# LED.net
KiCad netlist of a schematic drawn in Altium Designer
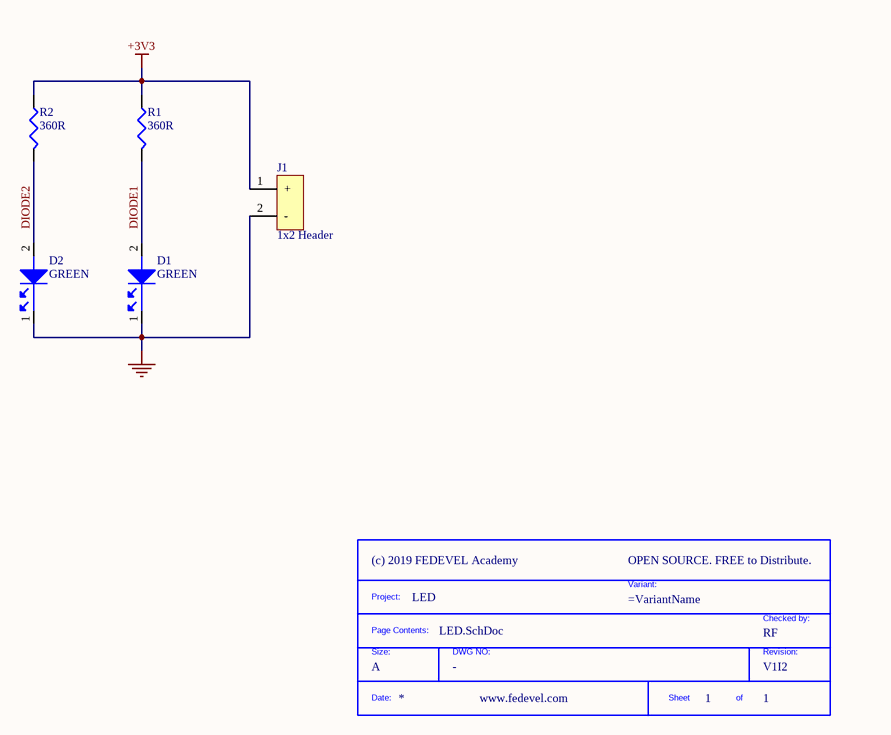
[diagram p0: LED.SchDoc]

(export (version "E")
  (design (tool "Eeschema 10.0.6"))
  (components
    (comp (ref "*")
      (value "TitleBlock")
      (description "Standard Title Block")
      (fields (field (name "DWG NO") "-") (field (name "SIZE") "A") (field (name "CHECKED BY") "RF"))
      (libsource (lib "LED_SchLib") (part "TitleBlock"))
    )
    (comp (ref "D1")
      (value "GREEN")
      (footprint "LED0603G")
      (description "Standard LEDs - SMD LED GR HI-BRT USS")
      (fields
        (field (name "MANUFACTURER") "Panasonic SSG")
        (field (name "MANUFACTURER PART NUMBER") "LNJ337W83RA")
      )
      (libsource (lib "LED_SchLib") (part "LNJ337W83RA"))
    )
    (comp (ref "D2")
      (value "GREEN")
      (footprint "LED0603G")
      (description "Standard LEDs - SMD LED GR HI-BRT USS")
      (fields
        (field (name "MANUFACTURER") "Panasonic SSG")
        (field (name "MANUFACTURER PART NUMBER") "LNJ337W83RA")
      )
      (libsource (lib "LED_SchLib") (part "LNJ337W83RA"))
    )
    (comp (ref "J1")
      (value "1x2 Header")
      (footprint "HDR1X2")
      (description "Headers & Wire Housings 2 PIN F/LK HEADER")
      (fields (field (name "MANUFACTURER") "Molex") (field (name "MANUFACTURER PART NUMBER") "22-29-2021"))
      (libsource (lib "LED_SchLib") (part "22-29-2021"))
    )
    (comp (ref "R1")
      (value "360R")
      (footprint "R0805")
      (description "RES SMD 360 OHM 1% 1/8W 0805")
      (fields
        (field (name "MANUFACTURER") "Vishay")
        (field (name "MANUFACTURER PART NUMBER") "CRCW0805360RFKEA")
      )
      (libsource (lib "LED_SchLib") (part "CRCW0805360RFKEA"))
    )
    (comp (ref "R2")
      (value "360R")
      (footprint "R0805")
      (description "RES SMD 360 OHM 1% 1/8W 0805")
      (fields
        (field (name "MANUFACTURER") "Vishay")
        (field (name "MANUFACTURER PART NUMBER") "CRCW0805360RFKEA")
      )
      (libsource (lib "LED_SchLib") (part "CRCW0805360RFKEA"))
    )
  )
  (nets
    (net (code "1") (name "+3V3") (class "Default")
      (node (ref "J1") (pin "1") (pinfunction "+_1") (pintype "passive"))
      (node (ref "R1") (pin "1") (pinfunction "1_1") (pintype "passive"))
      (node (ref "R2") (pin "1") (pinfunction "1_1") (pintype "passive"))
    )
    (net (code "2") (name "/DIODE1") (class "Default")
      (node (ref "D1") (pin "2") (pinfunction "2_2") (pintype "passive"))
      (node (ref "R1") (pin "2") (pinfunction "2_2") (pintype "passive"))
    )
    (net (code "3") (name "/DIODE2") (class "Default")
      (node (ref "D2") (pin "2") (pinfunction "2_2") (pintype "passive"))
      (node (ref "R2") (pin "2") (pinfunction "2_2") (pintype "passive"))
    )
    (net (code "4") (name "GND") (class "Default")
      (node (ref "D1") (pin "1") (pinfunction "1_1") (pintype "passive"))
      (node (ref "D2") (pin "1") (pinfunction "1_1") (pintype "passive"))
      (node (ref "J1") (pin "2") (pinfunction "-_2") (pintype "passive"))
    )
  )
)
